# ProPrj_STC_2_0.net
KiCad netlist of a schematic drawn in EasyEDA Pro
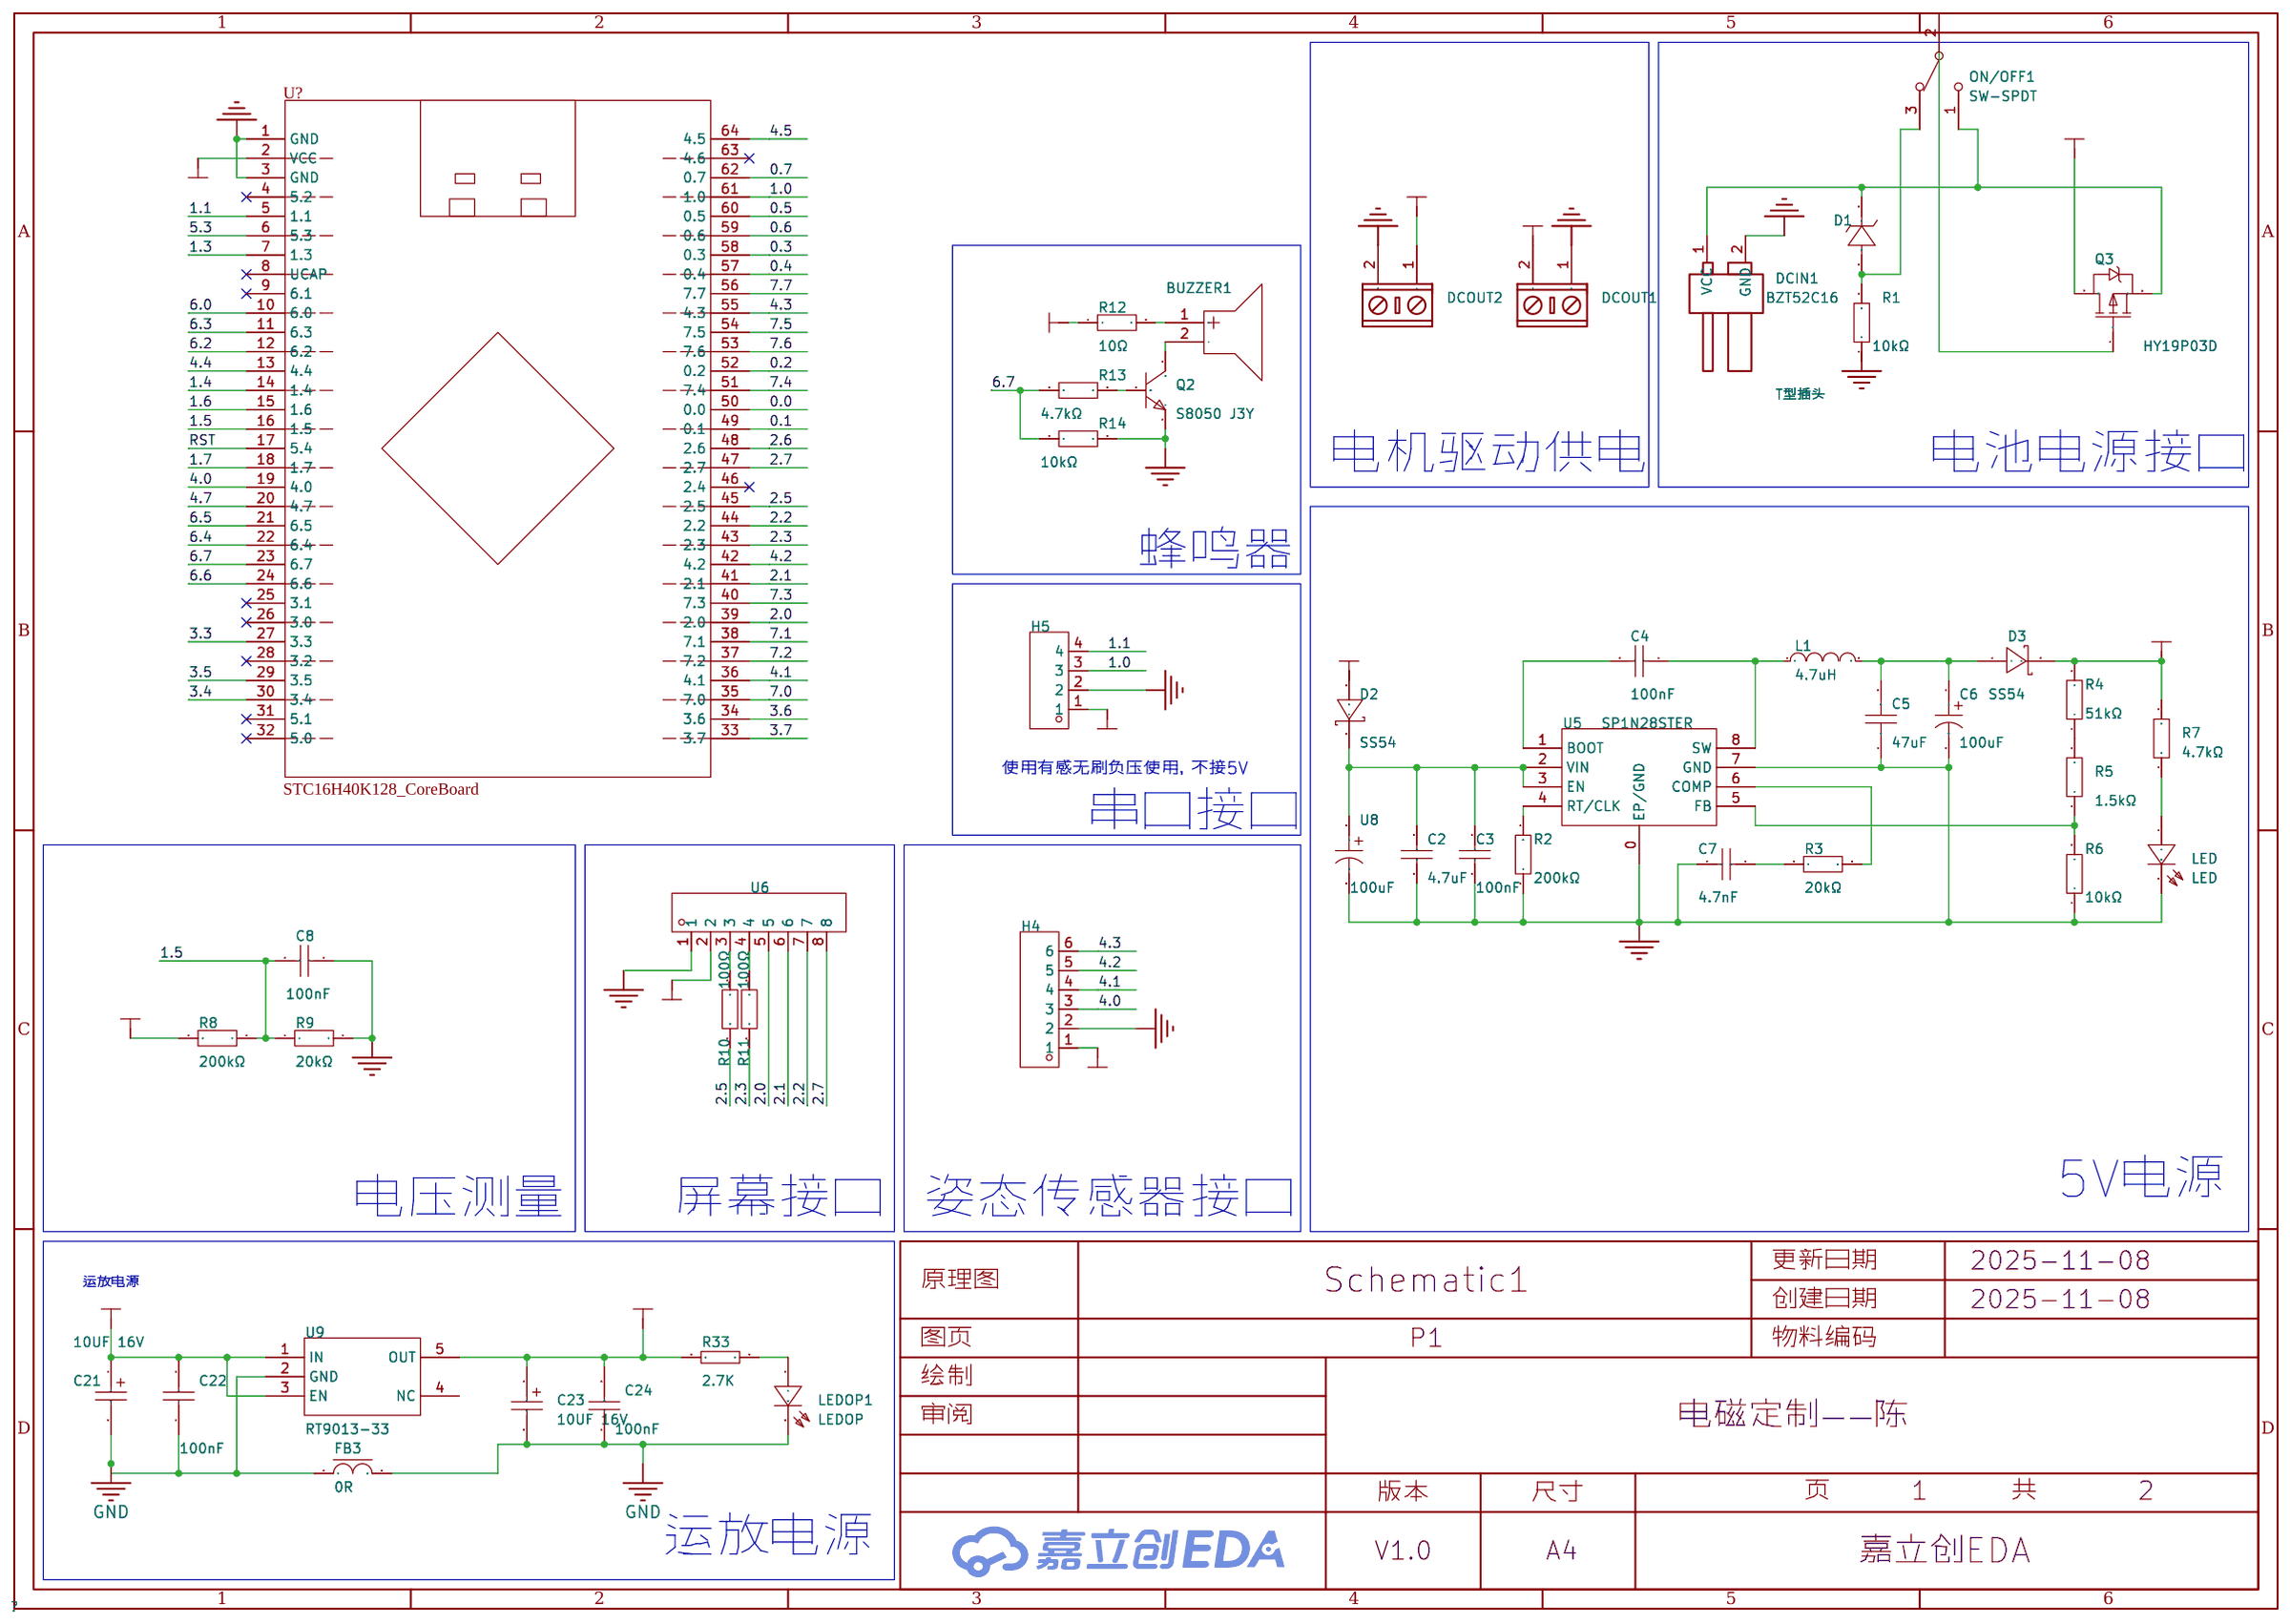
[diagram p0: P1]
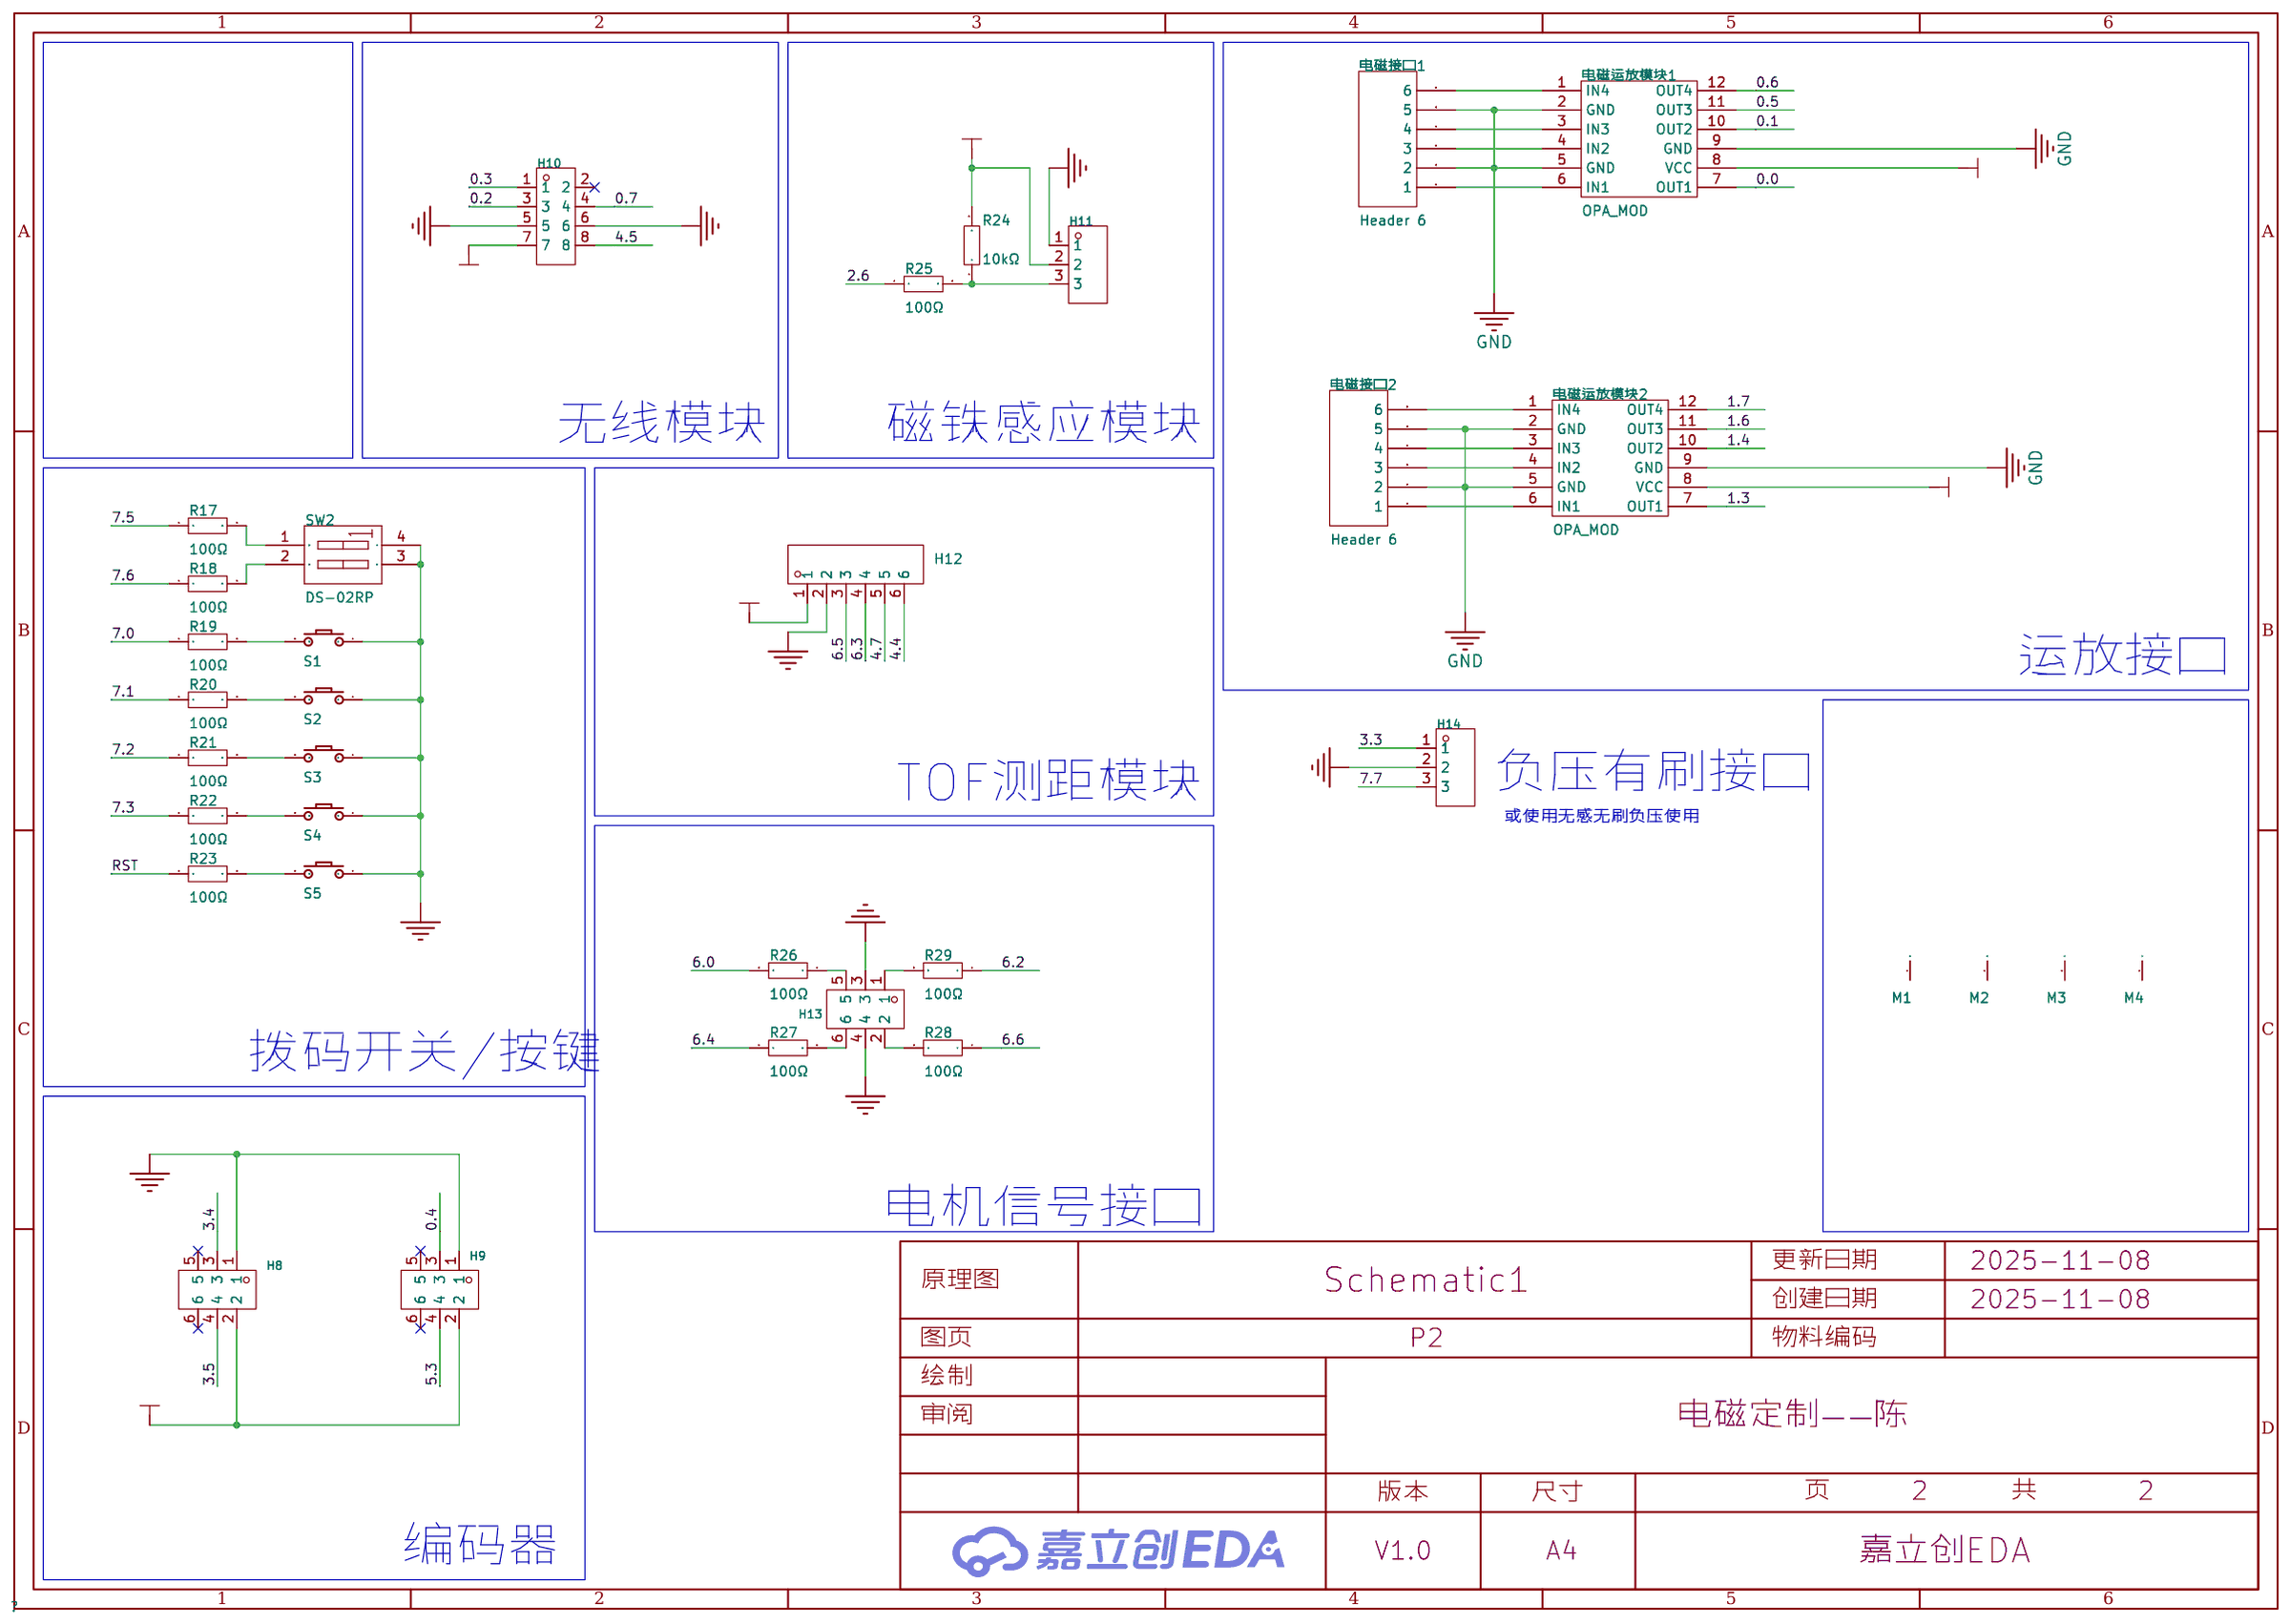
[diagram p1: P2]

(export (version "E")
  (design (tool "Eeschema 10.0.6"))
  (components
    (comp (ref "BUZZER1")
      (value "2.7kHz")
      (footprint "easyedapro:BUZ-TH_BD9.0-P4.00-D0.6-FD")
      (description "驱动方式:无源(外部驱动);构造类型:电磁式;频率:2.7kHz;声压(SPL):85dB@5V,10cm;")
      (fields
        (field (name "Manufacturer Part") "YS-MBZ9042C05R42")
        (field (name "Manufacturer") "Fengming(锋鸣电子)")
      )
      (libsource (lib "easyedapro") (part "YS-MBZ9042C05R42"))
    )
    (comp (ref "C2")
      (value "4.7uF")
      (footprint "easyedapro:C1206")
      (description "容值:4.7uF;精度:±10%;额定电压:50V;材质(温度系数):X7R;")
      (fields (field (name "Manufacturer Part") "1206B475K500NT") (field (name "Manufacturer") "FH(风华)"))
      (libsource (lib "easyedapro") (part "1206B475K500NT"))
    )
    (comp (ref "C3")
      (value "100nF")
      (footprint "easyedapro:C0603")
      (description "容值:100nF;精度:±10%;额定电压:50V;材质(温度系数):X7R;")
      (fields (field (name "Manufacturer Part") "0603B104K500NT") (field (name "Manufacturer") "FH(风华)"))
      (libsource (lib "easyedapro") (part "0603B104K500NT"))
    )
    (comp (ref "C4")
      (value "100nF")
      (footprint "easyedapro:C0603")
      (description "容值:100nF;精度:±10%;额定电压:50V;材质(温度系数):X7R;")
      (fields (field (name "Manufacturer Part") "0603B104K500NT") (field (name "Manufacturer") "FH(风华)"))
      (libsource (lib "easyedapro") (part "0603B104K500NT"))
    )
    (comp (ref "C5")
      (value "47uF")
      (footprint "easyedapro:C1206")
      (description "容值:47uF;精度:±20%;额定电压:25V;材质(温度系数):X5R;")
      (fields
        (field (name "Manufacturer Part") "GRM31CR61E476ME44L")
        (field (name "Manufacturer") "muRata(村田)")
      )
      (libsource (lib "easyedapro") (part "GRM31CR61E476ME44L"))
    )
    (comp (ref "C6")
      (value "100uF")
      (footprint "easyedapro:CAP-SMD_BD6.3-L6.6-W6.6-LS7.6-FD-1")
      (description "容值:100uF;精度:±20%;额定电压:35V;纹波电流:230mA@120Hz;等效串联电阻:600mΩ@100kHz;")
      (fields
        (field (name "Manufacturer Part") "RVE100UF35V67RV0072")
        (field (name "Manufacturer") "KNSCHA(科尼盛)")
      )
      (libsource (lib "easyedapro") (part "RVE100UF35V67RV0072"))
    )
    (comp (ref "C7")
      (value "4.7nF")
      (footprint "easyedapro:C0603")
      (description "容值:4.7nF;精度:±10%;额定电压:50V;材质(温度系数):X7R;")
      (fields (field (name "Manufacturer Part") "0603B472K500NT") (field (name "Manufacturer") "FH(风华)"))
      (libsource (lib "easyedapro") (part "0603B472K500NT"))
    )
    (comp (ref "C8")
      (value "100nF")
      (footprint "easyedapro:C0603")
      (description "容值:100nF;精度:±10%;额定电压:50V;材质(温度系数):X7R;")
      (fields (field (name "Manufacturer Part") "0603B104K500NT") (field (name "Manufacturer") "FH(风华)"))
      (libsource (lib "easyedapro") (part "0603B104K500NT"))
    )
    (comp (ref "C21")
      (value "10uF")
      (footprint "easyedapro:CAPT3216")
      (libsource (lib "easyedapro") (part "Cap-Tan"))
    )
    (comp (ref "C22")
      (value "100nF")
      (footprint "easyedapro:CAPC1608[0603]S-N")
      (libsource (lib "easyedapro") (part "Cap-Chip"))
    )
    (comp (ref "C23")
      (value "10uF")
      (footprint "easyedapro:CAPT3216")
      (libsource (lib "easyedapro") (part "Cap-Tan"))
    )
    (comp (ref "C24")
      (value "100nF")
      (footprint "easyedapro:CAPC1608[0603]S-N")
      (libsource (lib "easyedapro") (part "Cap-Chip"))
    )
    (comp (ref "D1")
      (value "BZT52C16")
      (footprint "easyedapro:SOD-123_L2.7-W1.7-LS3.8-RD")
      (description "二极管配置:独立式;稳压值(标称值):16V;稳压值(范围):15.3V~17.1V;功率:500mW;精度:-;")
      (fields (field (name "Manufacturer") "TWGMC(台湾迪嘉)"))
      (libsource (lib "easyedapro") (part "BZT52C16_C727007"))
    )
    (comp (ref "D2")
      (value "SS54")
      (footprint "easyedapro:SMA_L4.4-W2.8-LS5.4-R-RD")
      (description "正向压降(Vf):550mV@5A;直流反向耐压(Vr):40V;平均整流电流(Io):5A;")
      (fields (field (name "Manufacturer") "MDD"))
      (libsource (lib "easyedapro") (part "SS54_C22452"))
    )
    (comp (ref "D3")
      (value "SS54")
      (footprint "easyedapro:SMA_L4.4-W2.8-LS5.4-R-RD")
      (description "正向压降(Vf):550mV@5A;直流反向耐压(Vr):40V;平均整流电流(Io):5A;")
      (fields (field (name "Manufacturer") "MDD"))
      (libsource (lib "easyedapro") (part "SS54_C22452"))
    )
    (comp (ref "DCIN1")
      (value "T型插头")
      (footprint "easyedapro:Wired T-Header ThroughHole")
      (libsource (lib "easyedapro") (part "T_Header"))
    )
    (comp (ref "DCOUT1")
      (value "KF/WJ/DG 30x connecter")
      (footprint "easyedapro:KF/WJ/DG 301-2p-5.0mm")
      (description "接线端子 2Pin")
      (libsource (lib "easyedapro") (part "KF/WJ/DG 30x"))
    )
    (comp (ref "DCOUT2")
      (value "KF/WJ/DG 30x connecter")
      (footprint "easyedapro:KF/WJ/DG 301-2p-5.0mm")
      (description "接线端子 2Pin")
      (libsource (lib "easyedapro") (part "KF/WJ/DG 30x"))
    )
    (comp (ref "FB3")
      (value "0R")
      (footprint "easyedapro:INDC2012[0805]S")
      (libsource (lib "easyedapro") (part "Ind-Chip"))
    )
    (comp (ref "H4")
      (value "PZ254V-11-06P")
      (footprint "easyedapro:HDR-TH_6P-P2.54-V-M")
      (fields (field (name "Manufacturer") "XFCN(兴飞)"))
      (libsource (lib "easyedapro") (part "PZ254V-11-06P"))
    )
    (comp (ref "H5")
      (value "PZ254V-11-04P")
      (footprint "easyedapro:HDR-TH_4P-P2.54-V-M")
      (fields (field (name "Manufacturer") "XFCN(兴飞)"))
      (libsource (lib "easyedapro") (part "PZ254V-11-04P_C2691448"))
    )
    (comp (ref "L1")
      (value "4.7uH")
      (footprint "easyedapro:IND-SMD_L7.3-W6.6_MHCI06030")
      (description "电感值:2.2uH;精度:±20%;额定电流:10A;饱和电流(Isat):14A;")
      (fields
        (field (name "Manufacturer Part") "TMPC0605H-2R2MG-D")
        (field (name "Manufacturer") "TAI-TECH(台庆)")
      )
      (libsource (lib "easyedapro") (part "TMPC0605H-2R2MG-D"))
    )
    (comp (ref "LED")
      (value "LED")
      (footprint "easyedapro:LEDC1608(0603)")
      (libsource (lib "easyedapro") (part "LED Chip Green"))
    )
    (comp (ref "LEDOP1")
      (value "LEDOP")
      (footprint "easyedapro:LEDC1608(0603)")
      (libsource (lib "easyedapro") (part "LED Chip Green"))
    )
    (comp (ref "ON/OFF1")
      (value "SW-SPDT")
      (footprint "easyedapro:SS12D10")
      (libsource (lib "easyedapro") (part "SW-SPDT"))
    )
    (comp (ref "Q2")
      (value "S8050 J3Y")
      (footprint "easyedapro:SOT-23-3_L3.0-W1.7-P0.95-LS2.9-BR")
      (description "晶体管类型:NPN;集电极电流(Ic):500mA;集射极击穿电压(Vceo):25V;功率(Pd):300mW;直流电流增益(hFE@Ic,Vce):200@50mA,1V;")
      (fields (field (name "Manufacturer") "CJ(江苏长电/长晶)"))
      (libsource (lib "easyedapro") (part "S8050_C2146"))
    )
    (comp (ref "Q3")
      (value "HY19P03D")
      (footprint "easyedapro:TO-252-2_L6.6-W6.1-P4.57-LS9.9-TL-CW")
      (fields (field (name "Manufacturer") "HUAYI(华羿微)"))
      (libsource (lib "easyedapro") (part "HY19P03D"))
    )
    (comp (ref "R1")
      (value "10kΩ")
      (footprint "easyedapro:R0603")
      (description "电阻类型:厚膜电阻;阻值:10kΩ;精度:±1%;功率:100mW;最大工作电压:75V;温度系数:±100ppm/°C;")
      (fields
        (field (name "Manufacturer Part") "0603WAF1002T5E")
        (field (name "Manufacturer") "UNI-ROYAL(厚声)")
      )
      (libsource (lib "easyedapro") (part "0603WAF1002T5E"))
    )
    (comp (ref "R2")
      (value "200kΩ")
      (footprint "easyedapro:R0603")
      (description "电阻类型:厚膜电阻;阻值:200kΩ;精度:±1%;功率:100mW;最大工作电压:75V;温度系数:±100ppm/°C;")
      (fields
        (field (name "Manufacturer Part") "0603WAF2003T5E")
        (field (name "Manufacturer") "UNI-ROYAL(厚声)")
      )
      (libsource (lib "easyedapro") (part "0603WAF2003T5E"))
    )
    (comp (ref "R3")
      (value "20kΩ")
      (footprint "easyedapro:R0603")
      (description "电阻类型:厚膜电阻;阻值:20kΩ;精度:±1%;功率:100mW;最大工作电压:75V;温度系数:±100ppm/°C;")
      (fields
        (field (name "Manufacturer Part") "0603WAF2002T5E")
        (field (name "Manufacturer") "UNI-ROYAL(厚声)")
      )
      (libsource (lib "easyedapro") (part "0603WAF2002T5E"))
    )
    (comp (ref "R4")
      (value "51kΩ")
      (footprint "easyedapro:R0603")
      (description "电阻类型:厚膜电阻;阻值:51kΩ;精度:±1%;功率:100mW;最大工作电压:75V;温度系数:±100ppm/°C;")
      (fields
        (field (name "Manufacturer Part") "0603WAF5102T5E")
        (field (name "Manufacturer") "UNI-ROYAL(厚声)")
      )
      (libsource (lib "easyedapro") (part "0603WAF5102T5E"))
    )
    (comp (ref "R5")
      (value "1.5kΩ")
      (footprint "easyedapro:R0603")
      (description "电阻类型:厚膜电阻;阻值:1.5kΩ;精度:±1%;功率:100mW;最大工作电压:75V;温度系数:±100ppm/°C;")
      (fields
        (field (name "Manufacturer Part") "0603WAF1501T5E")
        (field (name "Manufacturer") "UNI-ROYAL(厚声)")
      )
      (libsource (lib "easyedapro") (part "0603WAF1501T5E"))
    )
    (comp (ref "R6")
      (value "10kΩ")
      (footprint "easyedapro:R0603")
      (description "电阻类型:厚膜电阻;阻值:10kΩ;精度:±1%;功率:100mW;最大工作电压:75V;温度系数:±100ppm/°C;")
      (fields
        (field (name "Manufacturer Part") "0603WAF1002T5E")
        (field (name "Manufacturer") "UNI-ROYAL(厚声)")
      )
      (libsource (lib "easyedapro") (part "0603WAF1002T5E"))
    )
    (comp (ref "R7")
      (value "4.7kΩ")
      (footprint "easyedapro:R0603")
      (description "电阻类型:厚膜电阻;阻值:4.7kΩ;精度:±1%;功率:100mW;最大工作电压:75V;温度系数:±100ppm/°C;")
      (fields
        (field (name "Manufacturer Part") "0603WAF4701T5E")
        (field (name "Manufacturer") "UNI-ROYAL(厚声)")
      )
      (libsource (lib "easyedapro") (part "0603WAF4701T5E"))
    )
    (comp (ref "R8")
      (value "200kΩ")
      (footprint "easyedapro:R0603")
      (description "电阻类型:厚膜电阻;阻值:200kΩ;精度:±1%;功率:100mW;最大工作电压:75V;温度系数:±100ppm/°C;")
      (fields
        (field (name "Manufacturer Part") "0603WAF2003T5E")
        (field (name "Manufacturer") "UNI-ROYAL(厚声)")
      )
      (libsource (lib "easyedapro") (part "0603WAF2003T5E"))
    )
    (comp (ref "R9")
      (value "20kΩ")
      (footprint "easyedapro:R0603")
      (description "电阻类型:厚膜电阻;阻值:20kΩ;精度:±1%;功率:100mW;最大工作电压:75V;温度系数:±100ppm/°C;")
      (fields
        (field (name "Manufacturer Part") "0603WAF2002T5E")
        (field (name "Manufacturer") "UNI-ROYAL(厚声)")
      )
      (libsource (lib "easyedapro") (part "0603WAF2002T5E"))
    )
    (comp (ref "R10")
      (value "100Ω")
      (footprint "easyedapro:R0603")
      (description "电阻类型:厚膜电阻;阻值:100Ω;精度:±1%;功率:100mW;最大工作电压:75V;温度系数:±100ppm/°C;")
      (fields (field (name "Manufacturer Part") "RC0603FR-07100RL") (field (name "Manufacturer") "YAGEO(国巨)"))
      (libsource (lib "easyedapro") (part "RC0603FR-07100RL"))
    )
    (comp (ref "R11")
      (value "100Ω")
      (footprint "easyedapro:R0603")
      (description "电阻类型:厚膜电阻;阻值:100Ω;精度:±1%;功率:100mW;最大工作电压:75V;温度系数:±100ppm/°C;")
      (fields (field (name "Manufacturer Part") "RC0603FR-07100RL") (field (name "Manufacturer") "YAGEO(国巨)"))
      (libsource (lib "easyedapro") (part "RC0603FR-07100RL"))
    )
    (comp (ref "R12")
      (value "10Ω")
      (footprint "easyedapro:R0603")
      (description "电阻类型:厚膜电阻;阻值:10Ω;精度:±1%;功率:100mW;最大工作电压:75V;温度系数:±400ppm/°C;")
      (fields
        (field (name "Manufacturer Part") "0603WAF100JT5E")
        (field (name "Manufacturer") "UNI-ROYAL(厚声)")
      )
      (libsource (lib "easyedapro") (part "0603WAF100JT5E"))
    )
    (comp (ref "R13")
      (value "4.7kΩ")
      (footprint "easyedapro:R0603")
      (description "电阻类型:厚膜电阻;阻值:4.7kΩ;精度:±1%;功率:100mW;最大工作电压:75V;温度系数:±100ppm/°C;")
      (fields
        (field (name "Manufacturer Part") "0603WAF4701T5E")
        (field (name "Manufacturer") "UNI-ROYAL(厚声)")
      )
      (libsource (lib "easyedapro") (part "0603WAF4701T5E"))
    )
    (comp (ref "R14")
      (value "10kΩ")
      (footprint "easyedapro:R0603")
      (description "电阻类型:厚膜电阻;阻值:10kΩ;精度:±1%;功率:100mW;最大工作电压:75V;温度系数:±100ppm/°C;")
      (fields
        (field (name "Manufacturer Part") "0603WAF1002T5E")
        (field (name "Manufacturer") "UNI-ROYAL(厚声)")
      )
      (libsource (lib "easyedapro") (part "0603WAF1002T5E"))
    )
    (comp (ref "R33")
      (value "4.7K")
      (footprint "easyedapro:RESC1608[0603]S-N")
      (libsource (lib "easyedapro") (part "Res-Chip_4"))
    )
    (comp (ref "U1") (value "~") (libsource (lib "easyedapro") (part "stc32")))
    (comp (ref "U5") (value "SP1N28STER") (libsource (lib "easyedapro") (part "SP1N28STER")))
    (comp (ref "U6")
      (value "PM254-1-08-Z-8.5")
      (footprint "easyedapro:HDR-TH_8P-P2.54-V-F")
      (fields (field (name "Manufacturer") "HCTL(华灿天禄)"))
      (libsource (lib "easyedapro") (part "PM254-1-08-Z-8.5"))
    )
    (comp (ref "U8")
      (value "100uF")
      (footprint "easyedapro:CAP-SMD_BD6.3-L6.6-W6.6-LS7.6-RD")
      (description "容值:100uF;精度:±20%;额定电压:50V;纹波电流:229mA@120Hz;")
      (fields (field (name "Manufacturer Part") "RVT1H101M0607") (field (name "Manufacturer") "ROQANG(容强)"))
      (libsource (lib "easyedapro") (part "RVT1H101M0607"))
    )
    (comp (ref "U9")
      (value "RT9013-33")
      (footprint "easyedapro:SOT-23-5")
      (libsource (lib "easyedapro") (part "RT9013-33"))
    )
    (comp (ref "H8")
      (value "PZ254V-12-6P")
      (footprint "easyedapro:HDR-TH_6P-P2.54-V-M-R2-C3-S2.54")
      (fields (field (name "Manufacturer") "XFCN(兴飞)"))
      (libsource (lib "easyedapro") (part "PZ254V-12-6P"))
    )
    (comp (ref "H9")
      (value "PZ254V-12-6P")
      (footprint "easyedapro:HDR-TH_6P-P2.54-V-M-R2-C3-S2.54")
      (fields (field (name "Manufacturer") "XFCN(兴飞)"))
      (libsource (lib "easyedapro") (part "PZ254V-12-6P"))
    )
    (comp (ref "H10")
      (value "PZ254V-12-8P")
      (footprint "easyedapro:HDR-TH_8P-P2.54-V-M-R2-C4-S2.54")
      (fields (field (name "Manufacturer") "XFCN(兴飞)"))
      (libsource (lib "easyedapro") (part "PZ254V-12-8P"))
    )
    (comp (ref "H11")
      (value "PZ254V-11-03P")
      (footprint "easyedapro:HDR-TH_3P-P2.54-V-M")
      (fields (field (name "Manufacturer") "XFCN(兴飞)"))
      (libsource (lib "easyedapro") (part "PZ254V-11-03P_C2937625"))
    )
    (comp (ref "H12")
      (value "PZ254V-11-06P")
      (footprint "easyedapro:HDR-TH_6P-P2.54-V-M")
      (fields (field (name "Manufacturer") "XFCN(兴飞)"))
      (libsource (lib "easyedapro") (part "PZ254V-11-06P"))
    )
    (comp (ref "H13")
      (value "PZ254V-12-6P")
      (footprint "easyedapro:HDR-TH_6P-P2.54-V-M-R2-C3-S2.54")
      (fields (field (name "Manufacturer") "XFCN(兴飞)"))
      (libsource (lib "easyedapro") (part "PZ254V-12-6P"))
    )
    (comp (ref "H14")
      (value "PZ254V-11-03P")
      (footprint "easyedapro:HDR-TH_3P-P2.54-V-M")
      (fields (field (name "Manufacturer") "XFCN(兴飞)"))
      (libsource (lib "easyedapro") (part "PZ254V-11-03P_C2937625"))
    )
    (comp (ref "M1")
      (value "MountHole")
      (footprint "easyedapro:M3-MountHole-Plated-D6")
      (description "固定孔")
      (libsource (lib "easyedapro") (part "MountHole"))
    )
    (comp (ref "M2")
      (value "MountHole")
      (footprint "easyedapro:M3-MountHole-Plated-D6")
      (description "固定孔")
      (libsource (lib "easyedapro") (part "MountHole"))
    )
    (comp (ref "M3")
      (value "MountHole")
      (footprint "easyedapro:M3-MountHole-Plated-D6")
      (description "固定孔")
      (libsource (lib "easyedapro") (part "MountHole"))
    )
    (comp (ref "M4")
      (value "MountHole")
      (footprint "easyedapro:M3-MountHole-Plated-D6")
      (description "固定孔")
      (libsource (lib "easyedapro") (part "MountHole"))
    )
    (comp (ref "R17")
      (value "100Ω")
      (footprint "easyedapro:R0603")
      (description "电阻类型:厚膜电阻;阻值:100Ω;精度:±1%;功率:100mW;最大工作电压:75V;温度系数:±100ppm/°C;")
      (fields (field (name "Manufacturer Part") "RC0603FR-07100RL") (field (name "Manufacturer") "YAGEO(国巨)"))
      (libsource (lib "easyedapro") (part "RC0603FR-07100RL"))
    )
    (comp (ref "R18")
      (value "100Ω")
      (footprint "easyedapro:R0603")
      (description "电阻类型:厚膜电阻;阻值:100Ω;精度:±1%;功率:100mW;最大工作电压:75V;温度系数:±100ppm/°C;")
      (fields (field (name "Manufacturer Part") "RC0603FR-07100RL") (field (name "Manufacturer") "YAGEO(国巨)"))
      (libsource (lib "easyedapro") (part "RC0603FR-07100RL"))
    )
    (comp (ref "R19")
      (value "100Ω")
      (footprint "easyedapro:R0603")
      (description "电阻类型:厚膜电阻;阻值:100Ω;精度:±1%;功率:100mW;最大工作电压:75V;温度系数:±100ppm/°C;")
      (fields (field (name "Manufacturer Part") "RC0603FR-07100RL") (field (name "Manufacturer") "YAGEO(国巨)"))
      (libsource (lib "easyedapro") (part "RC0603FR-07100RL"))
    )
    (comp (ref "R20")
      (value "100Ω")
      (footprint "easyedapro:R0603")
      (description "电阻类型:厚膜电阻;阻值:100Ω;精度:±1%;功率:100mW;最大工作电压:75V;温度系数:±100ppm/°C;")
      (fields (field (name "Manufacturer Part") "RC0603FR-07100RL") (field (name "Manufacturer") "YAGEO(国巨)"))
      (libsource (lib "easyedapro") (part "RC0603FR-07100RL"))
    )
    (comp (ref "R21")
      (value "100Ω")
      (footprint "easyedapro:R0603")
      (description "电阻类型:厚膜电阻;阻值:100Ω;精度:±1%;功率:100mW;最大工作电压:75V;温度系数:±100ppm/°C;")
      (fields (field (name "Manufacturer Part") "RC0603FR-07100RL") (field (name "Manufacturer") "YAGEO(国巨)"))
      (libsource (lib "easyedapro") (part "RC0603FR-07100RL"))
    )
    (comp (ref "R22")
      (value "100Ω")
      (footprint "easyedapro:R0603")
      (description "电阻类型:厚膜电阻;阻值:100Ω;精度:±1%;功率:100mW;最大工作电压:75V;温度系数:±100ppm/°C;")
      (fields (field (name "Manufacturer Part") "RC0603FR-07100RL") (field (name "Manufacturer") "YAGEO(国巨)"))
      (libsource (lib "easyedapro") (part "RC0603FR-07100RL"))
    )
    (comp (ref "R23")
      (value "100Ω")
      (footprint "easyedapro:R0603")
      (description "电阻类型:厚膜电阻;阻值:100Ω;精度:±1%;功率:100mW;最大工作电压:75V;温度系数:±100ppm/°C;")
      (fields (field (name "Manufacturer Part") "RC0603FR-07100RL") (field (name "Manufacturer") "YAGEO(国巨)"))
      (libsource (lib "easyedapro") (part "RC0603FR-07100RL"))
    )
    (comp (ref "R24")
      (value "10kΩ")
      (footprint "easyedapro:R0603")
      (description "电阻类型:厚膜电阻;阻值:10kΩ;精度:±1%;功率:100mW;最大工作电压:75V;温度系数:±100ppm/°C;")
      (fields
        (field (name "Manufacturer Part") "0603WAF1002T5E")
        (field (name "Manufacturer") "UNI-ROYAL(厚声)")
      )
      (libsource (lib "easyedapro") (part "0603WAF1002T5E"))
    )
    (comp (ref "R25")
      (value "100Ω")
      (footprint "easyedapro:R0603")
      (description "电阻类型:厚膜电阻;阻值:100Ω;精度:±1%;功率:100mW;最大工作电压:75V;温度系数:±100ppm/°C;")
      (fields (field (name "Manufacturer Part") "RC0603FR-07100RL") (field (name "Manufacturer") "YAGEO(国巨)"))
      (libsource (lib "easyedapro") (part "RC0603FR-07100RL"))
    )
    (comp (ref "R26")
      (value "100Ω")
      (footprint "easyedapro:R0603")
      (description "电阻类型:厚膜电阻;阻值:100Ω;精度:±1%;功率:100mW;最大工作电压:75V;温度系数:±100ppm/°C;")
      (fields (field (name "Manufacturer Part") "RC0603FR-07100RL") (field (name "Manufacturer") "YAGEO(国巨)"))
      (libsource (lib "easyedapro") (part "RC0603FR-07100RL"))
    )
    (comp (ref "R27")
      (value "100Ω")
      (footprint "easyedapro:R0603")
      (description "电阻类型:厚膜电阻;阻值:100Ω;精度:±1%;功率:100mW;最大工作电压:75V;温度系数:±100ppm/°C;")
      (fields (field (name "Manufacturer Part") "RC0603FR-07100RL") (field (name "Manufacturer") "YAGEO(国巨)"))
      (libsource (lib "easyedapro") (part "RC0603FR-07100RL"))
    )
    (comp (ref "R28")
      (value "100Ω")
      (footprint "easyedapro:R0603")
      (description "电阻类型:厚膜电阻;阻值:100Ω;精度:±1%;功率:100mW;最大工作电压:75V;温度系数:±100ppm/°C;")
      (fields (field (name "Manufacturer Part") "RC0603FR-07100RL") (field (name "Manufacturer") "YAGEO(国巨)"))
      (libsource (lib "easyedapro") (part "RC0603FR-07100RL"))
    )
    (comp (ref "R29")
      (value "100Ω")
      (footprint "easyedapro:R0603")
      (description "电阻类型:厚膜电阻;阻值:100Ω;精度:±1%;功率:100mW;最大工作电压:75V;温度系数:±100ppm/°C;")
      (fields (field (name "Manufacturer Part") "RC0603FR-07100RL") (field (name "Manufacturer") "YAGEO(国巨)"))
      (libsource (lib "easyedapro") (part "RC0603FR-07100RL"))
    )
    (comp (ref "S1")
      (value "Button")
      (footprint "easyedapro:PTS810-3*4-CurvePin")
      (description "按键")
      (libsource (lib "easyedapro") (part "KEY"))
    )
    (comp (ref "S2")
      (value "Button")
      (footprint "easyedapro:PTS810-3*4-CurvePin")
      (description "按键")
      (libsource (lib "easyedapro") (part "KEY"))
    )
    (comp (ref "S3")
      (value "Button")
      (footprint "easyedapro:PTS810-3*4-CurvePin")
      (description "按键")
      (libsource (lib "easyedapro") (part "KEY"))
    )
    (comp (ref "S4")
      (value "Button")
      (footprint "easyedapro:PTS810-3*4-CurvePin")
      (description "按键")
      (libsource (lib "easyedapro") (part "KEY"))
    )
    (comp (ref "S5")
      (value "Button")
      (footprint "easyedapro:PTS810-3*4-CurvePin")
      (description "按键")
      (libsource (lib "easyedapro") (part "KEY"))
    )
    (comp (ref "SW2")
      (value "DS-02RP")
      (footprint "easyedapro:SW-TH_DS-02XP")
      (description "类型:平拨,凸起式;电路结构:单刀单掷;开关位数:2位;额定电流:25mA;额定电压:24V;使用寿命:3千次;颜色:红色;")
      (fields (field (name "Manufacturer") "韩国韩荣"))
      (libsource (lib "easyedapro") (part "DS-02RP"))
    )
    (comp (ref "电磁接口1")
      (value "Header 6")
      (footprint "easyedapro:HDR1X6")
      (libsource (lib "easyedapro") (part "Header 6"))
    )
    (comp (ref "电磁接口2")
      (value "Header 6")
      (footprint "easyedapro:HDR1X6")
      (libsource (lib "easyedapro") (part "Header 6"))
    )
    (comp (ref "电磁运放模块1")
      (value "OPA_MOD")
      (footprint "easyedapro:SEEKFREE_4CHANEL_OPAMOD")
      (libsource (lib "easyedapro") (part "OPA_4CHANNEL_SEEKFREE"))
    )
    (comp (ref "电磁运放模块2")
      (value "OPA_MOD")
      (footprint "easyedapro:SEEKFREE_4CHANEL_OPAMOD")
      (libsource (lib "easyedapro") (part "OPA_4CHANNEL_SEEKFREE"))
    )
  )
  (nets
    (net (code "1") (name "0.0") (class "Default")
      (node (ref "U1") (pin "50") (pinfunction "0.0_50") (pintype "input"))
      (node (ref "电磁运放模块1") (pin "7") (pinfunction "OUT1_7") (pintype "input"))
    )
    (net (code "2") (name "0.1") (class "Default")
      (node (ref "U1") (pin "49") (pinfunction "0.1_49") (pintype "input"))
      (node (ref "电磁运放模块1") (pin "10") (pinfunction "OUT2_10") (pintype "input"))
    )
    (net (code "3") (name "0.2") (class "Default")
      (node (ref "H10") (pin "3") (pinfunction "3_3") (pintype "input"))
      (node (ref "U1") (pin "52") (pinfunction "0.2_52") (pintype "input"))
    )
    (net (code "4") (name "0.3") (class "Default")
      (node (ref "H10") (pin "1") (pinfunction "1_1") (pintype "input"))
      (node (ref "U1") (pin "58") (pinfunction "0.3_58") (pintype "input"))
    )
    (net (code "5") (name "0.4") (class "Default")
      (node (ref "H9") (pin "3") (pinfunction "3_3") (pintype "input"))
      (node (ref "U1") (pin "57") (pinfunction "0.4_57") (pintype "input"))
    )
    (net (code "6") (name "0.5") (class "Default")
      (node (ref "U1") (pin "60") (pinfunction "0.5_60") (pintype "input"))
      (node (ref "电磁运放模块1") (pin "11") (pinfunction "OUT3_11") (pintype "input"))
    )
    (net (code "7") (name "0.6") (class "Default")
      (node (ref "U1") (pin "59") (pinfunction "0.6_59") (pintype "input"))
      (node (ref "电磁运放模块1") (pin "12") (pinfunction "OUT4_12") (pintype "input"))
    )
    (net (code "8") (name "0.7") (class "Default")
      (node (ref "H10") (pin "4") (pinfunction "4_4") (pintype "input"))
      (node (ref "U1") (pin "62") (pinfunction "0.7_62") (pintype "input"))
    )
    (net (code "9") (name "1.0") (class "Default")
      (node (ref "H5") (pin "3") (pinfunction "3_3") (pintype "unspecified"))
      (node (ref "U1") (pin "61") (pinfunction "1.0_61") (pintype "input"))
    )
    (net (code "10") (name "1.1") (class "Default")
      (node (ref "H5") (pin "4") (pinfunction "4_4") (pintype "unspecified"))
      (node (ref "U1") (pin "5") (pinfunction "1.1_5") (pintype "input"))
    )
    (net (code "11") (name "1.3") (class "Default")
      (node (ref "U1") (pin "7") (pinfunction "1.3_7") (pintype "input"))
      (node (ref "电磁运放模块2") (pin "7") (pinfunction "OUT1_7") (pintype "input"))
    )
    (net (code "12") (name "1.4") (class "Default")
      (node (ref "U1") (pin "14") (pinfunction "1.4_14") (pintype "input"))
      (node (ref "电磁运放模块2") (pin "10") (pinfunction "OUT2_10") (pintype "input"))
    )
    (net (code "13") (name "1.5") (class "Default")
      (node (ref "C8") (pin "2") (pinfunction "2_2") (pintype "input"))
      (node (ref "R8") (pin "1") (pinfunction "1_1") (pintype "input"))
      (node (ref "R9") (pin "1") (pinfunction "1_1") (pintype "input"))
      (node (ref "U1") (pin "16") (pinfunction "1.5_16") (pintype "input"))
    )
    (net (code "14") (name "1.6") (class "Default")
      (node (ref "U1") (pin "15") (pinfunction "1.6_15") (pintype "input"))
      (node (ref "电磁运放模块2") (pin "11") (pinfunction "OUT3_11") (pintype "input"))
    )
    (net (code "15") (name "1.7") (class "Default")
      (node (ref "U1") (pin "18") (pinfunction "1.7_18") (pintype "input"))
      (node (ref "电磁运放模块2") (pin "12") (pinfunction "OUT4_12") (pintype "input"))
    )
    (net (code "16") (name "2.0") (class "Default")
      (node (ref "U1") (pin "39") (pinfunction "2.0_39") (pintype "input"))
      (node (ref "U6") (pin "5") (pinfunction "5_5") (pintype "unspecified"))
    )
    (net (code "17") (name "2.1") (class "Default")
      (node (ref "U1") (pin "41") (pinfunction "2.1_41") (pintype "input"))
      (node (ref "U6") (pin "6") (pinfunction "6_6") (pintype "unspecified"))
    )
    (net (code "18") (name "2.2") (class "Default")
      (node (ref "U1") (pin "44") (pinfunction "2.2_44") (pintype "input"))
      (node (ref "U6") (pin "7") (pinfunction "7_7") (pintype "unspecified"))
    )
    (net (code "19") (name "2.3") (class "Default")
      (node (ref "R11") (pin "2") (pinfunction "2_2") (pintype "input"))
      (node (ref "U1") (pin "43") (pinfunction "2.3_43") (pintype "input"))
    )
    (net (code "20") (name "2.5") (class "Default")
      (node (ref "R10") (pin "2") (pinfunction "2_2") (pintype "input"))
      (node (ref "U1") (pin "45") (pinfunction "2.5_45") (pintype "input"))
    )
    (net (code "21") (name "2.6") (class "Default")
      (node (ref "R25") (pin "1") (pinfunction "1_1") (pintype "input"))
      (node (ref "U1") (pin "48") (pinfunction "2.6_48") (pintype "input"))
    )
    (net (code "22") (name "2.7") (class "Default")
      (node (ref "U1") (pin "47") (pinfunction "2.7_47") (pintype "input"))
      (node (ref "U6") (pin "8") (pinfunction "8_8") (pintype "unspecified"))
    )
    (net (code "23") (name "3.3") (class "Default")
      (node (ref "H14") (pin "1") (pinfunction "1_1") (pintype "input"))
      (node (ref "U1") (pin "27") (pinfunction "3.3_27") (pintype "input"))
    )
    (net (code "24") (name "3.4") (class "Default")
      (node (ref "H8") (pin "3") (pinfunction "3_3") (pintype "input"))
      (node (ref "U1") (pin "30") (pinfunction "3.4_30") (pintype "input"))
    )
    (net (code "25") (name "3.5") (class "Default")
      (node (ref "H8") (pin "4") (pinfunction "4_4") (pintype "input"))
      (node (ref "U1") (pin "29") (pinfunction "3.5_29") (pintype "input"))
    )
    (net (code "26") (name "3.6") (class "Default")
      (node (ref "U1") (pin "34") (pinfunction "3.6_34") (pintype "input"))
    )
    (net (code "27") (name "3.7") (class "Default")
      (node (ref "U1") (pin "33") (pinfunction "3.7_33") (pintype "input"))
    )
    (net (code "28") (name "4.0") (class "Default")
      (node (ref "H4") (pin "3") (pinfunction "3_3") (pintype "unspecified"))
      (node (ref "U1") (pin "19") (pinfunction "4.0_19") (pintype "input"))
    )
    (net (code "29") (name "4.1") (class "Default")
      (node (ref "H4") (pin "4") (pinfunction "4_4") (pintype "unspecified"))
      (node (ref "U1") (pin "36") (pinfunction "4.1_36") (pintype "input"))
    )
    (net (code "30") (name "4.2") (class "Default")
      (node (ref "H4") (pin "5") (pinfunction "5_5") (pintype "unspecified"))
      (node (ref "U1") (pin "42") (pinfunction "4.2_42") (pintype "input"))
    )
    (net (code "31") (name "4.3") (class "Default")
      (node (ref "H4") (pin "6") (pinfunction "6_6") (pintype "unspecified"))
      (node (ref "U1") (pin "55") (pinfunction "4.3_55") (pintype "input"))
    )
    (net (code "32") (name "4.4") (class "Default")
      (node (ref "H12") (pin "6") (pinfunction "6_6") (pintype "unspecified"))
      (node (ref "U1") (pin "13") (pinfunction "4.4_13") (pintype "input"))
    )
    (net (code "33") (name "4.5") (class "Default")
      (node (ref "H10") (pin "8") (pinfunction "8_8") (pintype "input"))
      (node (ref "U1") (pin "64") (pinfunction "4.5_64") (pintype "input"))
    )
    (net (code "34") (name "4.7") (class "Default")
      (node (ref "H12") (pin "5") (pinfunction "5_5") (pintype "unspecified"))
      (node (ref "U1") (pin "20") (pinfunction "4.7_20") (pintype "input"))
    )
    (net (code "35") (name "5.3") (class "Default")
      (node (ref "H9") (pin "4") (pinfunction "4_4") (pintype "input"))
      (node (ref "U1") (pin "6") (pinfunction "5.3_6") (pintype "input"))
    )
    (net (code "36") (name "6.0") (class "Default")
      (node (ref "R26") (pin "2") (pinfunction "2_2") (pintype "input"))
      (node (ref "U1") (pin "10") (pinfunction "6.0_10") (pintype "input"))
    )
    (net (code "37") (name "6.2") (class "Default")
      (node (ref "R29") (pin "1") (pinfunction "1_1") (pintype "input"))
      (node (ref "U1") (pin "12") (pinfunction "6.2_12") (pintype "input"))
    )
    (net (code "38") (name "6.3") (class "Default")
      (node (ref "H12") (pin "4") (pinfunction "4_4") (pintype "unspecified"))
      (node (ref "U1") (pin "11") (pinfunction "6.3_11") (pintype "input"))
    )
    (net (code "39") (name "6.4") (class "Default")
      (node (ref "R27") (pin "1") (pinfunction "1_1") (pintype "input"))
      (node (ref "U1") (pin "22") (pinfunction "6.4_22") (pintype "input"))
    )
    (net (code "40") (name "6.5") (class "Default")
      (node (ref "H12") (pin "3") (pinfunction "3_3") (pintype "unspecified"))
      (node (ref "U1") (pin "21") (pinfunction "6.5_21") (pintype "input"))
    )
    (net (code "41") (name "6.6") (class "Default")
      (node (ref "R28") (pin "1") (pinfunction "1_1") (pintype "input"))
      (node (ref "U1") (pin "24") (pinfunction "6.6_24") (pintype "input"))
    )
    (net (code "42") (name "6.7") (class "Default")
      (node (ref "R13") (pin "1") (pinfunction "1_1") (pintype "input"))
      (node (ref "R14") (pin "1") (pinfunction "1_1") (pintype "input"))
      (node (ref "U1") (pin "23") (pinfunction "6.7_23") (pintype "input"))
    )
    (net (code "43") (name "7.0") (class "Default")
      (node (ref "R19") (pin "1") (pinfunction "1_1") (pintype "input"))
      (node (ref "U1") (pin "35") (pinfunction "7.0_35") (pintype "input"))
    )
    (net (code "44") (name "7.1") (class "Default")
      (node (ref "R20") (pin "1") (pinfunction "1_1") (pintype "input"))
      (node (ref "U1") (pin "38") (pinfunction "7.1_38") (pintype "input"))
    )
    (net (code "45") (name "7.2") (class "Default")
      (node (ref "R21") (pin "1") (pinfunction "1_1") (pintype "input"))
      (node (ref "U1") (pin "37") (pinfunction "7.2_37") (pintype "input"))
    )
    (net (code "46") (name "7.3") (class "Default")
      (node (ref "R22") (pin "1") (pinfunction "1_1") (pintype "input"))
      (node (ref "U1") (pin "40") (pinfunction "7.3_40") (pintype "input"))
    )
    (net (code "47") (name "7.4") (class "Default")
      (node (ref "U1") (pin "51") (pinfunction "7.4_51") (pintype "input"))
    )
    (net (code "48") (name "7.5") (class "Default")
      (node (ref "R17") (pin "1") (pinfunction "1_1") (pintype "input"))
      (node (ref "U1") (pin "54") (pinfunction "7.5_54") (pintype "input"))
    )
    (net (code "49") (name "7.6") (class "Default")
      (node (ref "R18") (pin "1") (pinfunction "1_1") (pintype "input"))
      (node (ref "U1") (pin "53") (pinfunction "7.6_53") (pintype "input"))
    )
    (net (code "50") (name "7.7") (class "Default")
      (node (ref "H14") (pin "3") (pinfunction "3_3") (pintype "input"))
      (node (ref "U1") (pin "56") (pinfunction "7.7_56") (pintype "input"))
    )
    (net (code "51") (name "GND") (class "Default")
      (node (ref "C2") (pin "1") (pinfunction "1_1") (pintype "input"))
      (node (ref "C21") (pin "2") (pinfunction "2_2") (pintype "input"))
      (node (ref "C22") (pin "1") (pinfunction "1_1") (pintype "input"))
      (node (ref "C23") (pin "2") (pinfunction "2_2") (pintype "input"))
      (node (ref "C24") (pin "1") (pinfunction "1_1") (pintype "input"))
      (node (ref "C3") (pin "1") (pinfunction "1_1") (pintype "input"))
      (node (ref "C5") (pin "1") (pinfunction "1_1") (pintype "unspecified"))
      (node (ref "C6") (pin "2") (pinfunction "2_2") (pintype "input"))
      (node (ref "C7") (pin "1") (pinfunction "1_1") (pintype "input"))
      (node (ref "C8") (pin "1") (pinfunction "1_1") (pintype "input"))
      (node (ref "DCIN1") (pin "2") (pinfunction "GND_2") (pintype "unspecified"))
      (node (ref "DCOUT1") (pin "1") (pinfunction "1_1") (pintype "unspecified"))
      (node (ref "DCOUT2") (pin "2") (pinfunction "2_2") (pintype "unspecified"))
      (node (ref "FB3") (pin "1") (pinfunction "1_1") (pintype "input"))
      (node (ref "FB3") (pin "2") (pinfunction "2_2") (pintype "input"))
      (node (ref "H10") (pin "5") (pinfunction "5_5") (pintype "input"))
      (node (ref "H10") (pin "6") (pinfunction "6_6") (pintype "input"))
      (node (ref "H11") (pin "1") (pinfunction "1_1") (pintype "input"))
      (node (ref "H12") (pin "2") (pinfunction "2_2") (pintype "unspecified"))
      (node (ref "H13") (pin "3") (pinfunction "3_3") (pintype "input"))
      (node (ref "H13") (pin "4") (pinfunction "4_4") (pintype "input"))
      (node (ref "H14") (pin "2") (pinfunction "2_2") (pintype "input"))
      (node (ref "H4") (pin "2") (pinfunction "2_2") (pintype "unspecified"))
      (node (ref "H5") (pin "2") (pinfunction "2_2") (pintype "unspecified"))
      (node (ref "H8") (pin "1") (pinfunction "1_1") (pintype "input"))
      (node (ref "H9") (pin "1") (pinfunction "1_1") (pintype "input"))
      (node (ref "LED") (pin "C") (pinfunction "C_C") (pintype "input"))
      (node (ref "LEDOP1") (pin "C") (pinfunction "C_C") (pintype "input"))
      (node (ref "Q2") (pin "2") (pinfunction "E_2") (pintype "unspecified"))
      (node (ref "R1") (pin "1") (pinfunction "1_1") (pintype "input"))
      (node (ref "R14") (pin "2") (pinfunction "2_2") (pintype "input"))
      (node (ref "R2") (pin "1") (pinfunction "1_1") (pintype "input"))
      (node (ref "R6") (pin "1") (pinfunction "1_1") (pintype "input"))
      (node (ref "R9") (pin "2") (pinfunction "2_2") (pintype "input"))
      (node (ref "S1") (pin "1") (pinfunction "1_1") (pintype "unspecified"))
      (node (ref "S2") (pin "1") (pinfunction "1_1") (pintype "unspecified"))
      (node (ref "S3") (pin "1") (pinfunction "1_1") (pintype "unspecified"))
      (node (ref "S4") (pin "1") (pinfunction "1_1") (pintype "unspecified"))
      (node (ref "S5") (pin "1") (pinfunction "1_1") (pintype "unspecified"))
      (node (ref "SW2") (pin "3") (pinfunction "3_3") (pintype "input"))
      (node (ref "SW2") (pin "4") (pinfunction "4_4") (pintype "input"))
      (node (ref "U1") (pin "1") (pinfunction "GND_1") (pintype "input"))
      (node (ref "U1") (pin "3") (pinfunction "GND_3") (pintype "input"))
      (node (ref "U5") (pin "0") (pinfunction "EP/GND_0") (pintype "input"))
      (node (ref "U5") (pin "7") (pinfunction "GND_7") (pintype "input"))
      (node (ref "U6") (pin "1") (pinfunction "1_1") (pintype "unspecified"))
      (node (ref "U8") (pin "2") (pinfunction "2_2") (pintype "input"))
      (node (ref "U9") (pin "2") (pinfunction "GND_2") (pintype "input"))
      (node (ref "电磁接口1") (pin "2") (pinfunction "2_2") (pintype "input"))
      (node (ref "电磁接口1") (pin "5") (pinfunction "5_5") (pintype "input"))
      (node (ref "电磁接口2") (pin "2") (pinfunction "2_2") (pintype "input"))
      (node (ref "电磁接口2") (pin "5") (pinfunction "5_5") (pintype "input"))
      (node (ref "电磁运放模块1") (pin "2") (pinfunction "GND_2") (pintype "input"))
      (node (ref "电磁运放模块1") (pin "5") (pinfunction "GND_5") (pintype "input"))
      (node (ref "电磁运放模块1") (pin "9") (pinfunction "GND_9") (pintype "input"))
      (node (ref "电磁运放模块2") (pin "2") (pinfunction "GND_2") (pintype "input"))
      (node (ref "电磁运放模块2") (pin "5") (pinfunction "GND_5") (pintype "input"))
      (node (ref "电磁运放模块2") (pin "9") (pinfunction "GND_9") (pintype "input"))
    )
    (net (code "52") (name "Net-(BUZZER1-+)") (class "Default")
      (node (ref "BUZZER1") (pin "1") (pinfunction "+_1") (pintype "unspecified"))
      (node (ref "R12") (pin "2") (pinfunction "2_2") (pintype "input"))
    )
    (net (code "53") (name "Net-(BUZZER1--)") (class "Default")
      (node (ref "BUZZER1") (pin "2") (pinfunction "-_2") (pintype "unspecified"))
      (node (ref "Q2") (pin "3") (pinfunction "C_3") (pintype "unspecified"))
    )
    (net (code "54") (name "Net-(C7-Pad2)") (class "Default")
      (node (ref "C7") (pin "2") (pinfunction "2_2") (pintype "input"))
      (node (ref "R3") (pin "1") (pinfunction "1_1") (pintype "input"))
    )
    (net (code "55") (name "Net-(D1-A)") (class "Default")
      (node (ref "D1") (pin "2") (pinfunction "A_2") (pintype "unspecified"))
      (node (ref "ON/OFF1") (pin "3") (pintype "input"))
      (node (ref "R1") (pin "2") (pinfunction "2_2") (pintype "input"))
    )
    (net (code "56") (name "Net-(D1-K)") (class "Default")
      (node (ref "D1") (pin "1") (pinfunction "K_1") (pintype "unspecified"))
      (node (ref "DCIN1") (pin "1") (pinfunction "VCC_1") (pintype "unspecified"))
      (node (ref "ON/OFF1") (pin "1") (pintype "input"))
      (node (ref "Q3") (pin "3") (pinfunction "S_3") (pintype "input"))
    )
    (net (code "57") (name "Net-(D2-K)") (class "Default")
      (node (ref "C2") (pin "2") (pinfunction "2_2") (pintype "input"))
      (node (ref "C3") (pin "2") (pinfunction "2_2") (pintype "input"))
      (node (ref "D2") (pin "2") (pinfunction "K_2") (pintype "unspecified"))
      (node (ref "U5") (pin "2") (pinfunction "VIN_2") (pintype "input"))
      (node (ref "U5") (pin "3") (pinfunction "EN_3") (pintype "input"))
      (node (ref "U8") (pin "1") (pinfunction "1_1") (pintype "input"))
    )
    (net (code "58") (name "Net-(D3-A)") (class "Default")
      (node (ref "C5") (pin "2") (pinfunction "2_2") (pintype "unspecified"))
      (node (ref "C6") (pin "1") (pinfunction "1_1") (pintype "input"))
      (node (ref "D3") (pin "1") (pinfunction "A_1") (pintype "unspecified"))
      (node (ref "L1") (pin "2") (pinfunction "2_2") (pintype "unspecified"))
    )
    (net (code "59") (name "Net-(H11-Pad3)") (class "Default")
      (node (ref "H11") (pin "3") (pinfunction "3_3") (pintype "input"))
      (node (ref "R24") (pin "1") (pinfunction "1_1") (pintype "input"))
      (node (ref "R25") (pin "2") (pinfunction "2_2") (pintype "input"))
    )
    (net (code "60") (name "Net-(H13-Pad1)") (class "Default")
      (node (ref "H13") (pin "1") (pinfunction "1_1") (pintype "input"))
      (node (ref "R29") (pin "2") (pinfunction "2_2") (pintype "input"))
    )
    (net (code "61") (name "Net-(H13-Pad2)") (class "Default")
      (node (ref "H13") (pin "2") (pinfunction "2_2") (pintype "input"))
      (node (ref "R28") (pin "2") (pinfunction "2_2") (pintype "input"))
    )
    (net (code "62") (name "Net-(H13-Pad5)") (class "Default")
      (node (ref "H13") (pin "5") (pinfunction "5_5") (pintype "input"))
      (node (ref "R26") (pin "1") (pinfunction "1_1") (pintype "input"))
    )
    (net (code "63") (name "Net-(H13-Pad6)") (class "Default")
      (node (ref "H13") (pin "6") (pinfunction "6_6") (pintype "input"))
      (node (ref "R27") (pin "2") (pinfunction "2_2") (pintype "input"))
    )
    (net (code "64") (name "Net-(LED-PadA)") (class "Default")
      (node (ref "LED") (pin "A") (pinfunction "A_A") (pintype "input"))
      (node (ref "R7") (pin "1") (pinfunction "1_1") (pintype "input"))
    )
    (net (code "65") (name "Net-(LEDOP1-PadA)") (class "Default")
      (node (ref "LEDOP1") (pin "A") (pinfunction "A_A") (pintype "input"))
      (node (ref "R33") (pin "1") (pinfunction "1_1") (pintype "input"))
    )
    (net (code "66") (name "Net-(Q2-B)") (class "Default")
      (node (ref "Q2") (pin "1") (pinfunction "B_1") (pintype "unspecified"))
      (node (ref "R13") (pin "2") (pinfunction "2_2") (pintype "input"))
    )
    (net (code "67") (name "Net-(Q3-G)") (class "Default")
      (node (ref "ON/OFF1") (pin "2") (pintype "input"))
      (node (ref "Q3") (pin "1") (pinfunction "G_1") (pintype "input"))
    )
    (net (code "68") (name "Net-(R4-Pad1)") (class "Default")
      (node (ref "R4") (pin "1") (pinfunction "1_1") (pintype "input"))
      (node (ref "R5") (pin "2") (pinfunction "2_2") (pintype "input"))
    )
    (net (code "69") (name "Net-(R10-Pad1)") (class "Default")
      (node (ref "R10") (pin "1") (pinfunction "1_1") (pintype "input"))
      (node (ref "U6") (pin "3") (pinfunction "3_3") (pintype "unspecified"))
    )
    (net (code "70") (name "Net-(R11-Pad1)") (class "Default")
      (node (ref "R11") (pin "1") (pinfunction "1_1") (pintype "input"))
      (node (ref "U6") (pin "4") (pinfunction "4_4") (pintype "unspecified"))
    )
    (net (code "71") (name "Net-(R19-Pad2)") (class "Default")
      (node (ref "R19") (pin "2") (pinfunction "2_2") (pintype "input"))
      (node (ref "S1") (pin "2") (pinfunction "2_2") (pintype "unspecified"))
    )
    (net (code "72") (name "Net-(R20-Pad2)") (class "Default")
      (node (ref "R20") (pin "2") (pinfunction "2_2") (pintype "input"))
      (node (ref "S2") (pin "2") (pinfunction "2_2") (pintype "unspecified"))
    )
    (net (code "73") (name "Net-(R21-Pad2)") (class "Default")
      (node (ref "R21") (pin "2") (pinfunction "2_2") (pintype "input"))
      (node (ref "S3") (pin "2") (pinfunction "2_2") (pintype "unspecified"))
    )
    (net (code "74") (name "Net-(R22-Pad2)") (class "Default")
      (node (ref "R22") (pin "2") (pinfunction "2_2") (pintype "input"))
      (node (ref "S4") (pin "2") (pinfunction "2_2") (pintype "unspecified"))
    )
    (net (code "75") (name "Net-(R23-Pad2)") (class "Default")
      (node (ref "R23") (pin "2") (pinfunction "2_2") (pintype "input"))
      (node (ref "S5") (pin "2") (pinfunction "2_2") (pintype "unspecified"))
    )
    (net (code "76") (name "Net-(SW2-A1)") (class "Default")
      (node (ref "R17") (pin "2") (pinfunction "2_2") (pintype "input"))
      (node (ref "SW2") (pin "1") (pinfunction "A1_1") (pintype "input"))
    )
    (net (code "77") (name "Net-(SW2-A2)") (class "Default")
      (node (ref "R18") (pin "2") (pinfunction "2_2") (pintype "input"))
      (node (ref "SW2") (pin "2") (pinfunction "A2_2") (pintype "input"))
    )
    (net (code "78") (name "Net-(U5-BOOT)") (class "Default")
      (node (ref "C4") (pin "2") (pinfunction "2_2") (pintype "input"))
      (node (ref "U5") (pin "1") (pinfunction "BOOT_1") (pintype "input"))
    )
    (net (code "79") (name "Net-(U5-COMP)") (class "Default")
      (node (ref "R3") (pin "2") (pinfunction "2_2") (pintype "input"))
      (node (ref "U5") (pin "6") (pinfunction "COMP_6") (pintype "input"))
    )
    (net (code "80") (name "Net-(U5-FB)") (class "Default")
      (node (ref "R5") (pin "1") (pinfunction "1_1") (pintype "input"))
      (node (ref "R6") (pin "2") (pinfunction "2_2") (pintype "input"))
      (node (ref "U5") (pin "5") (pinfunction "FB_5") (pintype "input"))
    )
    (net (code "81") (name "Net-(U5-RT{slash}CLK)") (class "Default")
      (node (ref "R2") (pin "2") (pinfunction "2_2") (pintype "input"))
      (node (ref "U5") (pin "4") (pinfunction "RT/CLK_4") (pintype "input"))
    )
    (net (code "82") (name "Net-(U5-SW)") (class "Default")
      (node (ref "C4") (pin "1") (pinfunction "1_1") (pintype "input"))
      (node (ref "L1") (pin "1") (pinfunction "1_1") (pintype "unspecified"))
      (node (ref "U5") (pin "8") (pinfunction "SW_8") (pintype "input"))
    )
    (net (code "83") (name "Net-(电磁运放模块1-IN1)") (class "Default")
      (node (ref "电磁接口1") (pin "1") (pinfunction "1_1") (pintype "input"))
      (node (ref "电磁运放模块1") (pin "6") (pinfunction "IN1_6") (pintype "input"))
    )
    (net (code "84") (name "Net-(电磁运放模块1-IN2)") (class "Default")
      (node (ref "电磁接口1") (pin "3") (pinfunction "3_3") (pintype "input"))
      (node (ref "电磁运放模块1") (pin "4") (pinfunction "IN2_4") (pintype "input"))
    )
    (net (code "85") (name "Net-(电磁运放模块1-IN3)") (class "Default")
      (node (ref "电磁接口1") (pin "4") (pinfunction "4_4") (pintype "input"))
      (node (ref "电磁运放模块1") (pin "3") (pinfunction "IN3_3") (pintype "input"))
    )
    (net (code "86") (name "Net-(电磁运放模块1-IN4)") (class "Default")
      (node (ref "电磁接口1") (pin "6") (pinfunction "6_6") (pintype "input"))
      (node (ref "电磁运放模块1") (pin "1") (pinfunction "IN4_1") (pintype "input"))
    )
    (net (code "87") (name "Net-(电磁运放模块2-IN1)") (class "Default")
      (node (ref "电磁接口2") (pin "1") (pinfunction "1_1") (pintype "input"))
      (node (ref "电磁运放模块2") (pin "6") (pinfunction "IN1_6") (pintype "input"))
    )
    (net (code "88") (name "Net-(电磁运放模块2-IN2)") (class "Default")
      (node (ref "电磁接口2") (pin "3") (pinfunction "3_3") (pintype "input"))
      (node (ref "电磁运放模块2") (pin "4") (pinfunction "IN2_4") (pintype "input"))
    )
    (net (code "89") (name "Net-(电磁运放模块2-IN3)") (class "Default")
      (node (ref "电磁接口2") (pin "4") (pinfunction "4_4") (pintype "input"))
      (node (ref "电磁运放模块2") (pin "3") (pinfunction "IN3_3") (pintype "input"))
    )
    (net (code "90") (name "Net-(电磁运放模块2-IN4)") (class "Default")
      (node (ref "电磁接口2") (pin "6") (pinfunction "6_6") (pintype "input"))
      (node (ref "电磁运放模块2") (pin "1") (pinfunction "IN4_1") (pintype "input"))
    )
    (net (code "91") (name "RST") (class "Default")
      (node (ref "R23") (pin "1") (pinfunction "1_1") (pintype "input"))
      (node (ref "U1") (pin "17") (pinfunction "5.4_17") (pintype "input"))
    )
    (net (code "92") (name "VBAT") (class "Default")
      (node (ref "D2") (pin "1") (pinfunction "A_1") (pintype "unspecified"))
      (node (ref "DCOUT1") (pin "2") (pinfunction "2_2") (pintype "unspecified"))
      (node (ref "DCOUT2") (pin "1") (pinfunction "1_1") (pintype "unspecified"))
      (node (ref "Q3") (pin "2") (pinfunction "D_2") (pintype "input"))
      (node (ref "R8") (pin "2") (pinfunction "2_2") (pintype "input"))
    )
    (net (code "93") (name "VCC5V") (class "Default")
      (node (ref "C21") (pin "1") (pinfunction "1_1") (pintype "input"))
      (node (ref "C22") (pin "2") (pinfunction "2_2") (pintype "input"))
      (node (ref "D3") (pin "2") (pinfunction "K_2") (pintype "unspecified"))
      (node (ref "H10") (pin "7") (pinfunction "7_7") (pintype "input"))
      (node (ref "H11") (pin "2") (pinfunction "2_2") (pintype "input"))
      (node (ref "H12") (pin "1") (pinfunction "1_1") (pintype "unspecified"))
      (node (ref "H4") (pin "1") (pinfunction "1_1") (pintype "unspecified"))
      (node (ref "H5") (pin "1") (pinfunction "1_1") (pintype "unspecified"))
      (node (ref "H8") (pin "2") (pinfunction "2_2") (pintype "input"))
      (node (ref "H9") (pin "2") (pinfunction "2_2") (pintype "input"))
      (node (ref "R12") (pin "1") (pinfunction "1_1") (pintype "input"))
      (node (ref "R24") (pin "2") (pinfunction "2_2") (pintype "input"))
      (node (ref "R4") (pin "2") (pinfunction "2_2") (pintype "input"))
      (node (ref "R7") (pin "2") (pinfunction "2_2") (pintype "input"))
      (node (ref "U1") (pin "2") (pinfunction "VCC_2") (pintype "input"))
      (node (ref "U6") (pin "2") (pinfunction "2_2") (pintype "unspecified"))
      (node (ref "U9") (pin "1") (pinfunction "IN_1") (pintype "input"))
      (node (ref "U9") (pin "3") (pinfunction "EN_3") (pintype "input"))
    )
    (net (code "94") (name "VCCOP") (class "Default")
      (node (ref "C23") (pin "1") (pinfunction "1_1") (pintype "input"))
      (node (ref "C24") (pin "2") (pinfunction "2_2") (pintype "input"))
      (node (ref "R33") (pin "2") (pinfunction "2_2") (pintype "input"))
      (node (ref "U9") (pin "5") (pinfunction "OUT_5") (pintype "input"))
      (node (ref "电磁运放模块1") (pin "8") (pinfunction "VCC_8") (pintype "input"))
      (node (ref "电磁运放模块2") (pin "8") (pinfunction "VCC_8") (pintype "input"))
    )
    (net (code "95") (name "unconnected-(H8-Pad5)") (class "Default")
      (node (ref "H8") (pin "5") (pinfunction "5_5") (pintype "input+no_connect"))
    )
    (net (code "96") (name "unconnected-(H8-Pad6)") (class "Default")
      (node (ref "H8") (pin "6") (pinfunction "6_6") (pintype "input+no_connect"))
    )
    (net (code "97") (name "unconnected-(H9-Pad5)") (class "Default")
      (node (ref "H9") (pin "5") (pinfunction "5_5") (pintype "input+no_connect"))
    )
    (net (code "98") (name "unconnected-(H9-Pad6)") (class "Default")
      (node (ref "H9") (pin "6") (pinfunction "6_6") (pintype "input+no_connect"))
    )
    (net (code "99") (name "unconnected-(H10-Pad2)") (class "Default")
      (node (ref "H10") (pin "2") (pinfunction "2_2") (pintype "input+no_connect"))
    )
    (net (code "100") (name "unconnected-(M1-Pad1)") (class "Default")
      (node (ref "M1") (pin "1") (pinfunction "1_1") (pintype "unspecified"))
    )
    (net (code "101") (name "unconnected-(M2-Pad1)") (class "Default")
      (node (ref "M2") (pin "1") (pinfunction "1_1") (pintype "unspecified"))
    )
    (net (code "102") (name "unconnected-(M3-Pad1)") (class "Default")
      (node (ref "M3") (pin "1") (pinfunction "1_1") (pintype "unspecified"))
    )
    (net (code "103") (name "unconnected-(M4-Pad1)") (class "Default")
      (node (ref "M4") (pin "1") (pinfunction "1_1") (pintype "unspecified"))
    )
    (net (code "104") (name "unconnected-(U1-2.4-Pad46)") (class "Default")
      (node (ref "U1") (pin "46") (pinfunction "2.4_46") (pintype "input+no_connect"))
    )
    (net (code "105") (name "unconnected-(U1-3.0-Pad26)") (class "Default")
      (node (ref "U1") (pin "26") (pinfunction "3.0_26") (pintype "input+no_connect"))
    )
    (net (code "106") (name "unconnected-(U1-3.1-Pad25)") (class "Default")
      (node (ref "U1") (pin "25") (pinfunction "3.1_25") (pintype "input+no_connect"))
    )
    (net (code "107") (name "unconnected-(U1-3.2-Pad28)") (class "Default")
      (node (ref "U1") (pin "28") (pinfunction "3.2_28") (pintype "input+no_connect"))
    )
    (net (code "108") (name "unconnected-(U1-4.6-Pad63)") (class "Default")
      (node (ref "U1") (pin "63") (pinfunction "4.6_63") (pintype "input+no_connect"))
    )
    (net (code "109") (name "unconnected-(U1-5.0-Pad32)") (class "Default")
      (node (ref "U1") (pin "32") (pinfunction "5.0_32") (pintype "input+no_connect"))
    )
    (net (code "110") (name "unconnected-(U1-5.1-Pad31)") (class "Default")
      (node (ref "U1") (pin "31") (pinfunction "5.1_31") (pintype "input+no_connect"))
    )
    (net (code "111") (name "unconnected-(U1-5.2-Pad4)") (class "Default")
      (node (ref "U1") (pin "4") (pinfunction "5.2_4") (pintype "input+no_connect"))
    )
    (net (code "112") (name "unconnected-(U1-6.1-Pad9)") (class "Default")
      (node (ref "U1") (pin "9") (pinfunction "6.1_9") (pintype "input+no_connect"))
    )
    (net (code "113") (name "unconnected-(U1-UCAP-Pad8)") (class "Default")
      (node (ref "U1") (pin "8") (pinfunction "UCAP_8") (pintype "input+no_connect"))
    )
    (net (code "114") (name "unconnected-(U9-NC-Pad4)") (class "Default")
      (node (ref "U9") (pin "4") (pinfunction "NC_4") (pintype "input"))
    )
  )
)
